# motors_motherBoard_simple_panel.net
KiCad netlist of a schematic drawn in EAGLE
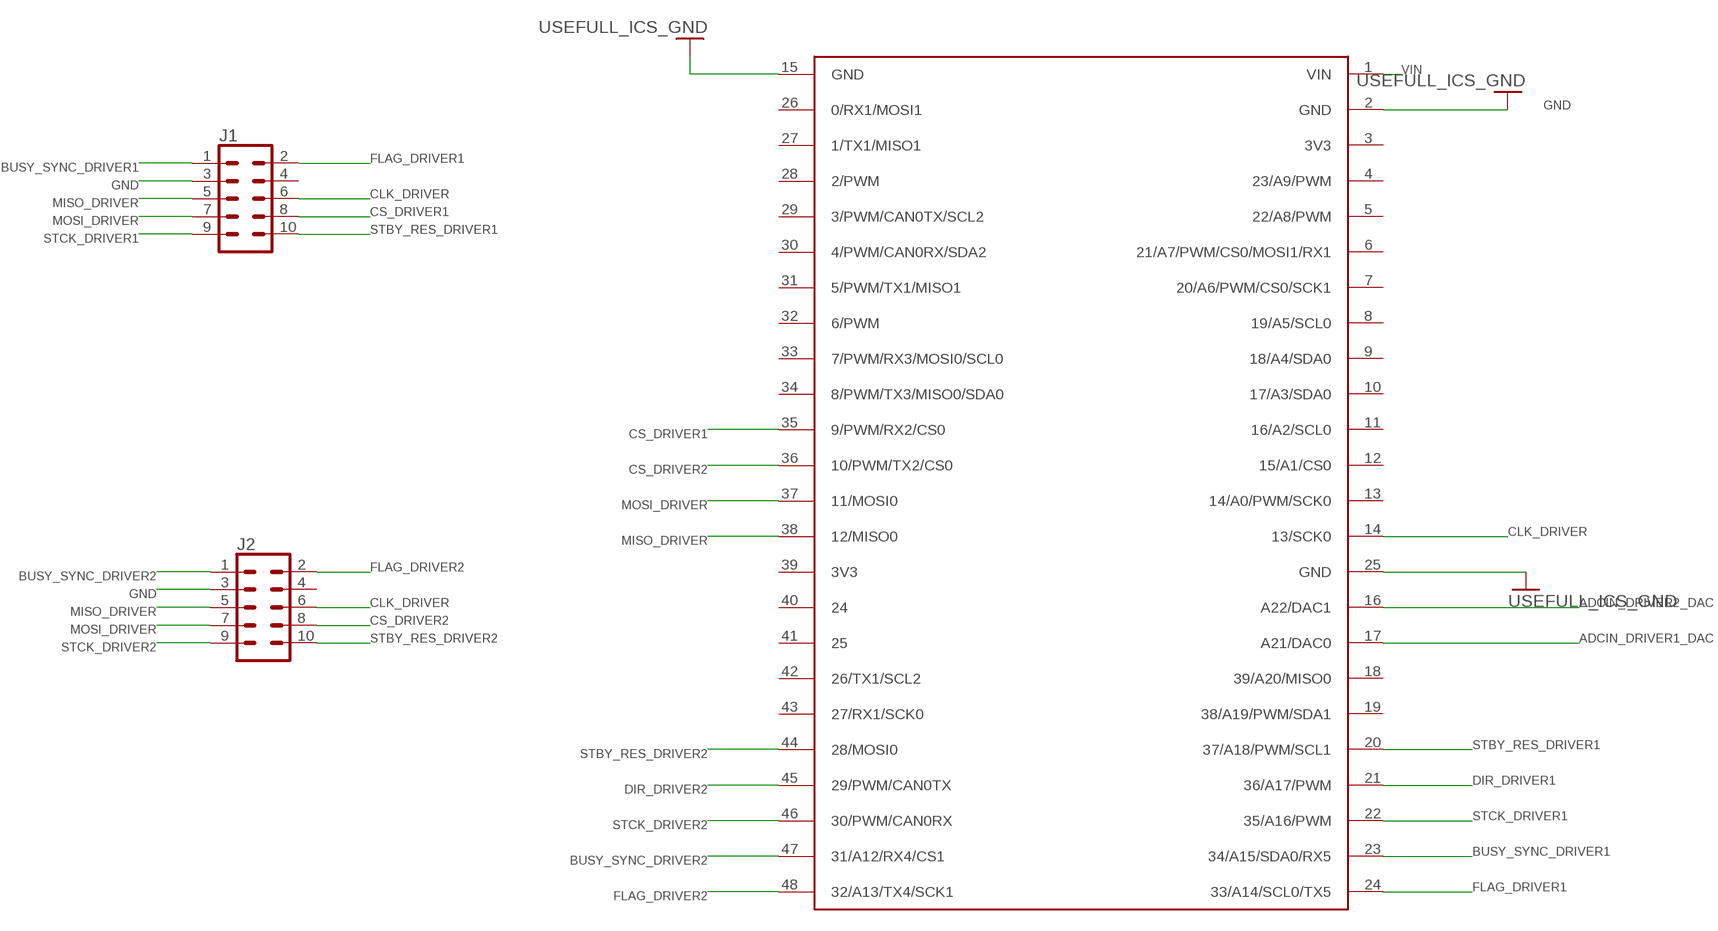
[diagram p0: schematic, sheet 1]
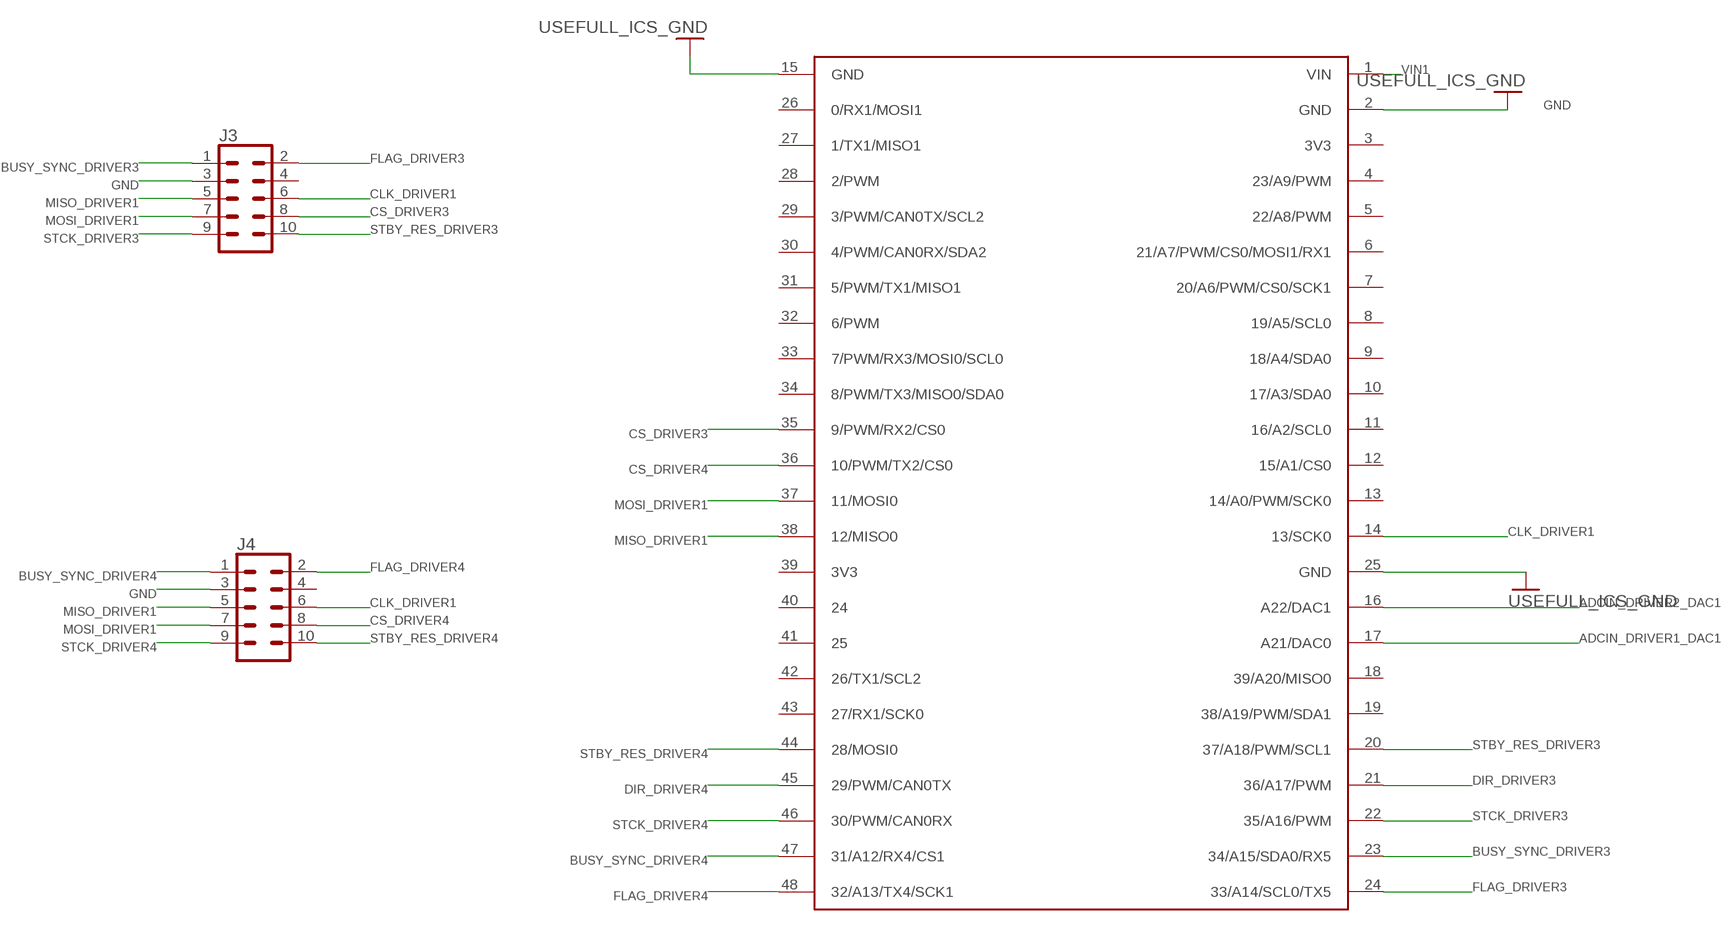
[diagram p1: schematic, sheet 2]

(export (version "E")
  (design (tool "Eeschema 10.0.6"))
  (components
    (comp (ref "J3")
      (value "SPARKFUN-CONNECTORS_CONN_05X2SHD_LOCK")
      (footprint "eagle-import:SPARKFUN-CONNECTORS_2X5-SHROUDED_LOCK")
      (libsource (lib "eagle-import") (part "SPARKFUN-CONNECTORS_CONN_05X2SHD_LOCK"))
    )
    (comp (ref "J4")
      (value "SPARKFUN-CONNECTORS_CONN_05X2SHD_LOCK")
      (footprint "eagle-import:SPARKFUN-CONNECTORS_2X5-SHROUDED_LOCK")
      (libsource (lib "eagle-import") (part "SPARKFUN-CONNECTORS_CONN_05X2SHD_LOCK"))
    )
    (comp (ref "U$1")
      (value "USEFULL_ICS_TEENSY_BASE_ADAPTER")
      (footprint "eagle-import:USEFULL_ICS_TEENSY_BASE_ADAPTER")
      (libsource (lib "eagle-import") (part "USEFULL_ICS_TEENSY_BASE_ADAPTER"))
    )
    (comp (ref "J1")
      (value "SPARKFUN-CONNECTORS_CONN_05X2SHD_LOCK")
      (footprint "eagle-import:SPARKFUN-CONNECTORS_2X5-SHROUDED_LOCK")
      (libsource (lib "eagle-import") (part "SPARKFUN-CONNECTORS_CONN_05X2SHD_LOCK"))
    )
    (comp (ref "J2")
      (value "SPARKFUN-CONNECTORS_CONN_05X2SHD_LOCK")
      (footprint "eagle-import:SPARKFUN-CONNECTORS_2X5-SHROUDED_LOCK")
      (libsource (lib "eagle-import") (part "SPARKFUN-CONNECTORS_CONN_05X2SHD_LOCK"))
    )
    (comp (ref "U$3")
      (value "USEFULL_ICS_TEENSY_BASE_ADAPTER")
      (footprint "eagle-import:USEFULL_ICS_TEENSY_BASE_ADAPTER")
      (libsource (lib "eagle-import") (part "USEFULL_ICS_TEENSY_BASE_ADAPTER"))
    )
  )
  (nets
    (net (code "1") (name "ADCIN_DRIVER1_DAC") (class "Default")
      (node (ref "U$3") (pin "17") (pinfunction "A21/DAC0_17") (pintype "bidirectional"))
    )
    (net (code "2") (name "ADCIN_DRIVER1_DAC1") (class "Default")
      (node (ref "U$1") (pin "17") (pinfunction "A21/DAC0_17") (pintype "bidirectional"))
    )
    (net (code "3") (name "ADCIN_DRIVER2_DAC") (class "Default")
      (node (ref "U$3") (pin "16") (pinfunction "A22/DAC1_16") (pintype "bidirectional"))
    )
    (net (code "4") (name "ADCIN_DRIVER2_DAC1") (class "Default")
      (node (ref "U$1") (pin "16") (pinfunction "A22/DAC1_16") (pintype "bidirectional"))
    )
    (net (code "5") (name "BUSY_SYNC_DRIVER1") (class "Default")
      (node (ref "J1") (pin "1") (pinfunction "1_1") (pintype "passive"))
      (node (ref "U$3") (pin "23") (pinfunction "34/A15/SDA0/RX5_23") (pintype "bidirectional"))
    )
    (net (code "6") (name "BUSY_SYNC_DRIVER2") (class "Default")
      (node (ref "J2") (pin "1") (pinfunction "1_1") (pintype "passive"))
      (node (ref "U$3") (pin "47") (pinfunction "31/A12/RX4/CS1_47") (pintype "bidirectional"))
    )
    (net (code "7") (name "BUSY_SYNC_DRIVER3") (class "Default")
      (node (ref "J3") (pin "1") (pinfunction "1_1") (pintype "passive"))
      (node (ref "U$1") (pin "23") (pinfunction "34/A15/SDA0/RX5_23") (pintype "bidirectional"))
    )
    (net (code "8") (name "BUSY_SYNC_DRIVER4") (class "Default")
      (node (ref "J4") (pin "1") (pinfunction "1_1") (pintype "passive"))
      (node (ref "U$1") (pin "47") (pinfunction "31/A12/RX4/CS1_47") (pintype "bidirectional"))
    )
    (net (code "9") (name "CLK_DRIVER") (class "Default")
      (node (ref "J1") (pin "6") (pinfunction "6_6") (pintype "passive"))
      (node (ref "J2") (pin "6") (pinfunction "6_6") (pintype "passive"))
      (node (ref "U$3") (pin "14") (pinfunction "13/SCK0_14") (pintype "bidirectional"))
    )
    (net (code "10") (name "CLK_DRIVER1") (class "Default")
      (node (ref "J3") (pin "6") (pinfunction "6_6") (pintype "passive"))
      (node (ref "J4") (pin "6") (pinfunction "6_6") (pintype "passive"))
      (node (ref "U$1") (pin "14") (pinfunction "13/SCK0_14") (pintype "bidirectional"))
    )
    (net (code "11") (name "CS_DRIVER1") (class "Default")
      (node (ref "J1") (pin "8") (pinfunction "8_8") (pintype "passive"))
      (node (ref "U$3") (pin "35") (pinfunction "9/PWM/RX2/CS0_35") (pintype "bidirectional"))
    )
    (net (code "12") (name "CS_DRIVER2") (class "Default")
      (node (ref "J2") (pin "8") (pinfunction "8_8") (pintype "passive"))
      (node (ref "U$3") (pin "36") (pinfunction "10/PWM/TX2/CS0_36") (pintype "bidirectional"))
    )
    (net (code "13") (name "CS_DRIVER3") (class "Default")
      (node (ref "J3") (pin "8") (pinfunction "8_8") (pintype "passive"))
      (node (ref "U$1") (pin "35") (pinfunction "9/PWM/RX2/CS0_35") (pintype "bidirectional"))
    )
    (net (code "14") (name "CS_DRIVER4") (class "Default")
      (node (ref "J4") (pin "8") (pinfunction "8_8") (pintype "passive"))
      (node (ref "U$1") (pin "36") (pinfunction "10/PWM/TX2/CS0_36") (pintype "bidirectional"))
    )
    (net (code "15") (name "DIR_DRIVER1") (class "Default")
      (node (ref "U$3") (pin "21") (pinfunction "36/A17/PWM_21") (pintype "bidirectional"))
    )
    (net (code "16") (name "DIR_DRIVER2") (class "Default")
      (node (ref "U$3") (pin "45") (pinfunction "29/PWM/CAN0TX_45") (pintype "bidirectional"))
    )
    (net (code "17") (name "DIR_DRIVER3") (class "Default")
      (node (ref "U$1") (pin "21") (pinfunction "36/A17/PWM_21") (pintype "bidirectional"))
    )
    (net (code "18") (name "DIR_DRIVER4") (class "Default")
      (node (ref "U$1") (pin "45") (pinfunction "29/PWM/CAN0TX_45") (pintype "bidirectional"))
    )
    (net (code "19") (name "FLAG_DRIVER1") (class "Default")
      (node (ref "J1") (pin "2") (pinfunction "2_2") (pintype "passive"))
      (node (ref "U$3") (pin "24") (pinfunction "33/A14/SCL0/TX5_24") (pintype "bidirectional"))
    )
    (net (code "20") (name "FLAG_DRIVER2") (class "Default")
      (node (ref "J2") (pin "2") (pinfunction "2_2") (pintype "passive"))
      (node (ref "U$3") (pin "48") (pinfunction "32/A13/TX4/SCK1_48") (pintype "bidirectional"))
    )
    (net (code "21") (name "FLAG_DRIVER3") (class "Default")
      (node (ref "J3") (pin "2") (pinfunction "2_2") (pintype "passive"))
      (node (ref "U$1") (pin "24") (pinfunction "33/A14/SCL0/TX5_24") (pintype "bidirectional"))
    )
    (net (code "22") (name "FLAG_DRIVER4") (class "Default")
      (node (ref "J4") (pin "2") (pinfunction "2_2") (pintype "passive"))
      (node (ref "U$1") (pin "48") (pinfunction "32/A13/TX4/SCK1_48") (pintype "bidirectional"))
    )
    (net (code "23") (name "GND") (class "Default")
      (node (ref "J1") (pin "3") (pinfunction "3_3") (pintype "passive"))
      (node (ref "J2") (pin "3") (pinfunction "3_3") (pintype "passive"))
      (node (ref "J3") (pin "3") (pinfunction "3_3") (pintype "passive"))
      (node (ref "J4") (pin "3") (pinfunction "3_3") (pintype "passive"))
      (node (ref "U$1") (pin "15") (pinfunction "GND_15") (pintype "bidirectional"))
      (node (ref "U$1") (pin "2") (pinfunction "GND_2") (pintype "bidirectional"))
      (node (ref "U$1") (pin "25") (pinfunction "GND_25") (pintype "bidirectional"))
      (node (ref "U$3") (pin "15") (pinfunction "GND_15") (pintype "bidirectional"))
      (node (ref "U$3") (pin "2") (pinfunction "GND_2") (pintype "bidirectional"))
      (node (ref "U$3") (pin "25") (pinfunction "GND_25") (pintype "bidirectional"))
    )
    (net (code "24") (name "MISO_DRIVER") (class "Default")
      (node (ref "J1") (pin "5") (pinfunction "5_5") (pintype "passive"))
      (node (ref "J2") (pin "5") (pinfunction "5_5") (pintype "passive"))
      (node (ref "U$3") (pin "38") (pinfunction "12/MISO0_38") (pintype "bidirectional"))
    )
    (net (code "25") (name "MISO_DRIVER1") (class "Default")
      (node (ref "J3") (pin "5") (pinfunction "5_5") (pintype "passive"))
      (node (ref "J4") (pin "5") (pinfunction "5_5") (pintype "passive"))
      (node (ref "U$1") (pin "38") (pinfunction "12/MISO0_38") (pintype "bidirectional"))
    )
    (net (code "26") (name "MOSI_DRIVER") (class "Default")
      (node (ref "J1") (pin "7") (pinfunction "7_7") (pintype "passive"))
      (node (ref "J2") (pin "7") (pinfunction "7_7") (pintype "passive"))
      (node (ref "U$3") (pin "37") (pinfunction "11/MOSI0_37") (pintype "bidirectional"))
    )
    (net (code "27") (name "MOSI_DRIVER1") (class "Default")
      (node (ref "J3") (pin "7") (pinfunction "7_7") (pintype "passive"))
      (node (ref "J4") (pin "7") (pinfunction "7_7") (pintype "passive"))
      (node (ref "U$1") (pin "37") (pinfunction "11/MOSI0_37") (pintype "bidirectional"))
    )
    (net (code "28") (name "STBY_RES_DRIVER1") (class "Default")
      (node (ref "J1") (pin "10") (pinfunction "10_10") (pintype "passive"))
      (node (ref "U$3") (pin "20") (pinfunction "37/A18/PWM/SCL1_20") (pintype "bidirectional"))
    )
    (net (code "29") (name "STBY_RES_DRIVER2") (class "Default")
      (node (ref "J2") (pin "10") (pinfunction "10_10") (pintype "passive"))
      (node (ref "U$3") (pin "44") (pinfunction "28/MOSI0_44") (pintype "bidirectional"))
    )
    (net (code "30") (name "STBY_RES_DRIVER3") (class "Default")
      (node (ref "J3") (pin "10") (pinfunction "10_10") (pintype "passive"))
      (node (ref "U$1") (pin "20") (pinfunction "37/A18/PWM/SCL1_20") (pintype "bidirectional"))
    )
    (net (code "31") (name "STBY_RES_DRIVER4") (class "Default")
      (node (ref "J4") (pin "10") (pinfunction "10_10") (pintype "passive"))
      (node (ref "U$1") (pin "44") (pinfunction "28/MOSI0_44") (pintype "bidirectional"))
    )
    (net (code "32") (name "STCK_DRIVER1") (class "Default")
      (node (ref "J1") (pin "9") (pinfunction "9_9") (pintype "passive"))
      (node (ref "U$3") (pin "22") (pinfunction "35/A16/PWM_22") (pintype "bidirectional"))
    )
    (net (code "33") (name "STCK_DRIVER2") (class "Default")
      (node (ref "J2") (pin "9") (pinfunction "9_9") (pintype "passive"))
      (node (ref "U$3") (pin "46") (pinfunction "30/PWM/CAN0RX_46") (pintype "bidirectional"))
    )
    (net (code "34") (name "STCK_DRIVER3") (class "Default")
      (node (ref "J3") (pin "9") (pinfunction "9_9") (pintype "passive"))
      (node (ref "U$1") (pin "22") (pinfunction "35/A16/PWM_22") (pintype "bidirectional"))
    )
    (net (code "35") (name "STCK_DRIVER4") (class "Default")
      (node (ref "J4") (pin "9") (pinfunction "9_9") (pintype "passive"))
      (node (ref "U$1") (pin "46") (pinfunction "30/PWM/CAN0RX_46") (pintype "bidirectional"))
    )
    (net (code "36") (name "VIN") (class "Default")
      (node (ref "U$3") (pin "1") (pinfunction "VIN_1") (pintype "bidirectional"))
    )
    (net (code "37") (name "VIN1") (class "Default")
      (node (ref "U$1") (pin "1") (pinfunction "VIN_1") (pintype "bidirectional"))
    )
    (net (code "38") (name "unconnected-(J1-Pad4)") (class "Default")
      (node (ref "J1") (pin "4") (pinfunction "4_4") (pintype "passive"))
    )
    (net (code "39") (name "unconnected-(J2-Pad4)") (class "Default")
      (node (ref "J2") (pin "4") (pinfunction "4_4") (pintype "passive"))
    )
    (net (code "40") (name "unconnected-(J3-Pad4)") (class "Default")
      (node (ref "J3") (pin "4") (pinfunction "4_4") (pintype "passive"))
    )
    (net (code "41") (name "unconnected-(J4-Pad4)") (class "Default")
      (node (ref "J4") (pin "4") (pinfunction "4_4") (pintype "passive"))
    )
    (net (code "42") (name "unconnected-(U$1-0{slash}RX1{slash}MOSI1-Pad26)") (class "Default")
      (node (ref "U$1") (pin "26") (pinfunction "0/RX1/MOSI1_26") (pintype "bidirectional"))
    )
    (net (code "43") (name "unconnected-(U$1-1{slash}TX1{slash}MISO1-Pad27)") (class "Default")
      (node (ref "U$1") (pin "27") (pinfunction "1/TX1/MISO1_27") (pintype "bidirectional"))
    )
    (net (code "44") (name "unconnected-(U$1-2{slash}PWM-Pad28)") (class "Default")
      (node (ref "U$1") (pin "28") (pinfunction "2/PWM_28") (pintype "bidirectional"))
    )
    (net (code "45") (name "unconnected-(U$1-3V3-Pad3)") (class "Default")
      (node (ref "U$1") (pin "3") (pinfunction "3V3_3") (pintype "bidirectional"))
    )
    (net (code "46") (name "unconnected-(U$1-3V3-Pad39)") (class "Default")
      (node (ref "U$1") (pin "39") (pinfunction "3V3_39") (pintype "bidirectional"))
    )
    (net (code "47") (name "unconnected-(U$1-3{slash}PWM{slash}CAN0TX{slash}SCL2-Pad29)") (class "Default")
      (node (ref "U$1") (pin "29") (pinfunction "3/PWM/CAN0TX/SCL2_29") (pintype "bidirectional"))
    )
    (net (code "48") (name "unconnected-(U$1-4{slash}PWM{slash}CAN0RX{slash}SDA2-Pad30)") (class "Default")
      (node (ref "U$1") (pin "30") (pinfunction "4/PWM/CAN0RX/SDA2_30") (pintype "bidirectional"))
    )
    (net (code "49") (name "unconnected-(U$1-5{slash}PWM{slash}TX1{slash}MISO1-Pad31)") (class "Default")
      (node (ref "U$1") (pin "31") (pinfunction "5/PWM/TX1/MISO1_31") (pintype "bidirectional"))
    )
    (net (code "50") (name "unconnected-(U$1-6{slash}PWM-Pad32)") (class "Default")
      (node (ref "U$1") (pin "32") (pinfunction "6/PWM_32") (pintype "bidirectional"))
    )
    (net (code "51") (name "unconnected-(U$1-7{slash}PWM{slash}RX3{slash}MOSI0{slash}SCL0-Pad33)") (class "Default")
      (node (ref "U$1") (pin "33") (pinfunction "7/PWM/RX3/MOSI0/SCL0_33") (pintype "bidirectional"))
    )
    (net (code "52") (name "unconnected-(U$1-8{slash}PWM{slash}TX3{slash}MISO0{slash}SDA0-Pad34)") (class "Default")
      (node (ref "U$1") (pin "34") (pinfunction "8/PWM/TX3/MISO0/SDA0_34") (pintype "bidirectional"))
    )
    (net (code "53") (name "unconnected-(U$1-14{slash}A0{slash}PWM{slash}SCK0-Pad13)") (class "Default")
      (node (ref "U$1") (pin "13") (pinfunction "14/A0/PWM/SCK0_13") (pintype "bidirectional"))
    )
    (net (code "54") (name "unconnected-(U$1-15{slash}A1{slash}CS0-Pad12)") (class "Default")
      (node (ref "U$1") (pin "12") (pinfunction "15/A1/CS0_12") (pintype "bidirectional"))
    )
    (net (code "55") (name "unconnected-(U$1-16{slash}A2{slash}SCL0-Pad11)") (class "Default")
      (node (ref "U$1") (pin "11") (pinfunction "16/A2/SCL0_11") (pintype "bidirectional"))
    )
    (net (code "56") (name "unconnected-(U$1-17{slash}A3{slash}SDA0-Pad10)") (class "Default")
      (node (ref "U$1") (pin "10") (pinfunction "17/A3/SDA0_10") (pintype "bidirectional"))
    )
    (net (code "57") (name "unconnected-(U$1-18{slash}A4{slash}SDA0-Pad9)") (class "Default")
      (node (ref "U$1") (pin "9") (pinfunction "18/A4/SDA0_9") (pintype "bidirectional"))
    )
    (net (code "58") (name "unconnected-(U$1-19{slash}A5{slash}SCL0-Pad8)") (class "Default")
      (node (ref "U$1") (pin "8") (pinfunction "19/A5/SCL0_8") (pintype "bidirectional"))
    )
    (net (code "59") (name "unconnected-(U$1-20{slash}A6{slash}PWM{slash}CS0{slash}SCK1-Pad7)") (class "Default")
      (node (ref "U$1") (pin "7") (pinfunction "20/A6/PWM/CS0/SCK1_7") (pintype "bidirectional"))
    )
    (net (code "60") (name "unconnected-(U$1-21{slash}A7{slash}PWM{slash}CS0{slash}MOSI1{slash}RX1-Pad6)") (class "Default")
      (node (ref "U$1") (pin "6") (pinfunction "21/A7/PWM/CS0/MOSI1/RX1_6") (pintype "bidirectional"))
    )
    (net (code "61") (name "unconnected-(U$1-22{slash}A8{slash}PWM-Pad5)") (class "Default")
      (node (ref "U$1") (pin "5") (pinfunction "22/A8/PWM_5") (pintype "bidirectional"))
    )
    (net (code "62") (name "unconnected-(U$1-23{slash}A9{slash}PWM-Pad4)") (class "Default")
      (node (ref "U$1") (pin "4") (pinfunction "23/A9/PWM_4") (pintype "bidirectional"))
    )
    (net (code "63") (name "unconnected-(U$1-24-Pad40)") (class "Default")
      (node (ref "U$1") (pin "40") (pinfunction "24_40") (pintype "bidirectional"))
    )
    (net (code "64") (name "unconnected-(U$1-25-Pad41)") (class "Default")
      (node (ref "U$1") (pin "41") (pinfunction "25_41") (pintype "bidirectional"))
    )
    (net (code "65") (name "unconnected-(U$1-26{slash}TX1{slash}SCL2-Pad42)") (class "Default")
      (node (ref "U$1") (pin "42") (pinfunction "26/TX1/SCL2_42") (pintype "bidirectional"))
    )
    (net (code "66") (name "unconnected-(U$1-27{slash}RX1{slash}SCK0-Pad43)") (class "Default")
      (node (ref "U$1") (pin "43") (pinfunction "27/RX1/SCK0_43") (pintype "bidirectional"))
    )
    (net (code "67") (name "unconnected-(U$1-38{slash}A19{slash}PWM{slash}SDA1-Pad19)") (class "Default")
      (node (ref "U$1") (pin "19") (pinfunction "38/A19/PWM/SDA1_19") (pintype "bidirectional"))
    )
    (net (code "68") (name "unconnected-(U$1-39{slash}A20{slash}MISO0-Pad18)") (class "Default")
      (node (ref "U$1") (pin "18") (pinfunction "39/A20/MISO0_18") (pintype "bidirectional"))
    )
    (net (code "69") (name "unconnected-(U$3-0{slash}RX1{slash}MOSI1-Pad26)") (class "Default")
      (node (ref "U$3") (pin "26") (pinfunction "0/RX1/MOSI1_26") (pintype "bidirectional"))
    )
    (net (code "70") (name "unconnected-(U$3-1{slash}TX1{slash}MISO1-Pad27)") (class "Default")
      (node (ref "U$3") (pin "27") (pinfunction "1/TX1/MISO1_27") (pintype "bidirectional"))
    )
    (net (code "71") (name "unconnected-(U$3-2{slash}PWM-Pad28)") (class "Default")
      (node (ref "U$3") (pin "28") (pinfunction "2/PWM_28") (pintype "bidirectional"))
    )
    (net (code "72") (name "unconnected-(U$3-3V3-Pad3)") (class "Default")
      (node (ref "U$3") (pin "3") (pinfunction "3V3_3") (pintype "bidirectional"))
    )
    (net (code "73") (name "unconnected-(U$3-3V3-Pad39)") (class "Default")
      (node (ref "U$3") (pin "39") (pinfunction "3V3_39") (pintype "bidirectional"))
    )
    (net (code "74") (name "unconnected-(U$3-3{slash}PWM{slash}CAN0TX{slash}SCL2-Pad29)") (class "Default")
      (node (ref "U$3") (pin "29") (pinfunction "3/PWM/CAN0TX/SCL2_29") (pintype "bidirectional"))
    )
    (net (code "75") (name "unconnected-(U$3-4{slash}PWM{slash}CAN0RX{slash}SDA2-Pad30)") (class "Default")
      (node (ref "U$3") (pin "30") (pinfunction "4/PWM/CAN0RX/SDA2_30") (pintype "bidirectional"))
    )
    (net (code "76") (name "unconnected-(U$3-5{slash}PWM{slash}TX1{slash}MISO1-Pad31)") (class "Default")
      (node (ref "U$3") (pin "31") (pinfunction "5/PWM/TX1/MISO1_31") (pintype "bidirectional"))
    )
    (net (code "77") (name "unconnected-(U$3-6{slash}PWM-Pad32)") (class "Default")
      (node (ref "U$3") (pin "32") (pinfunction "6/PWM_32") (pintype "bidirectional"))
    )
    (net (code "78") (name "unconnected-(U$3-7{slash}PWM{slash}RX3{slash}MOSI0{slash}SCL0-Pad33)") (class "Default")
      (node (ref "U$3") (pin "33") (pinfunction "7/PWM/RX3/MOSI0/SCL0_33") (pintype "bidirectional"))
    )
    (net (code "79") (name "unconnected-(U$3-8{slash}PWM{slash}TX3{slash}MISO0{slash}SDA0-Pad34)") (class "Default")
      (node (ref "U$3") (pin "34") (pinfunction "8/PWM/TX3/MISO0/SDA0_34") (pintype "bidirectional"))
    )
    (net (code "80") (name "unconnected-(U$3-14{slash}A0{slash}PWM{slash}SCK0-Pad13)") (class "Default")
      (node (ref "U$3") (pin "13") (pinfunction "14/A0/PWM/SCK0_13") (pintype "bidirectional"))
    )
    (net (code "81") (name "unconnected-(U$3-15{slash}A1{slash}CS0-Pad12)") (class "Default")
      (node (ref "U$3") (pin "12") (pinfunction "15/A1/CS0_12") (pintype "bidirectional"))
    )
    (net (code "82") (name "unconnected-(U$3-16{slash}A2{slash}SCL0-Pad11)") (class "Default")
      (node (ref "U$3") (pin "11") (pinfunction "16/A2/SCL0_11") (pintype "bidirectional"))
    )
    (net (code "83") (name "unconnected-(U$3-17{slash}A3{slash}SDA0-Pad10)") (class "Default")
      (node (ref "U$3") (pin "10") (pinfunction "17/A3/SDA0_10") (pintype "bidirectional"))
    )
    (net (code "84") (name "unconnected-(U$3-18{slash}A4{slash}SDA0-Pad9)") (class "Default")
      (node (ref "U$3") (pin "9") (pinfunction "18/A4/SDA0_9") (pintype "bidirectional"))
    )
    (net (code "85") (name "unconnected-(U$3-19{slash}A5{slash}SCL0-Pad8)") (class "Default")
      (node (ref "U$3") (pin "8") (pinfunction "19/A5/SCL0_8") (pintype "bidirectional"))
    )
    (net (code "86") (name "unconnected-(U$3-20{slash}A6{slash}PWM{slash}CS0{slash}SCK1-Pad7)") (class "Default")
      (node (ref "U$3") (pin "7") (pinfunction "20/A6/PWM/CS0/SCK1_7") (pintype "bidirectional"))
    )
    (net (code "87") (name "unconnected-(U$3-21{slash}A7{slash}PWM{slash}CS0{slash}MOSI1{slash}RX1-Pad6)") (class "Default")
      (node (ref "U$3") (pin "6") (pinfunction "21/A7/PWM/CS0/MOSI1/RX1_6") (pintype "bidirectional"))
    )
    (net (code "88") (name "unconnected-(U$3-22{slash}A8{slash}PWM-Pad5)") (class "Default")
      (node (ref "U$3") (pin "5") (pinfunction "22/A8/PWM_5") (pintype "bidirectional"))
    )
    (net (code "89") (name "unconnected-(U$3-23{slash}A9{slash}PWM-Pad4)") (class "Default")
      (node (ref "U$3") (pin "4") (pinfunction "23/A9/PWM_4") (pintype "bidirectional"))
    )
    (net (code "90") (name "unconnected-(U$3-24-Pad40)") (class "Default")
      (node (ref "U$3") (pin "40") (pinfunction "24_40") (pintype "bidirectional"))
    )
    (net (code "91") (name "unconnected-(U$3-25-Pad41)") (class "Default")
      (node (ref "U$3") (pin "41") (pinfunction "25_41") (pintype "bidirectional"))
    )
    (net (code "92") (name "unconnected-(U$3-26{slash}TX1{slash}SCL2-Pad42)") (class "Default")
      (node (ref "U$3") (pin "42") (pinfunction "26/TX1/SCL2_42") (pintype "bidirectional"))
    )
    (net (code "93") (name "unconnected-(U$3-27{slash}RX1{slash}SCK0-Pad43)") (class "Default")
      (node (ref "U$3") (pin "43") (pinfunction "27/RX1/SCK0_43") (pintype "bidirectional"))
    )
    (net (code "94") (name "unconnected-(U$3-38{slash}A19{slash}PWM{slash}SDA1-Pad19)") (class "Default")
      (node (ref "U$3") (pin "19") (pinfunction "38/A19/PWM/SDA1_19") (pintype "bidirectional"))
    )
    (net (code "95") (name "unconnected-(U$3-39{slash}A20{slash}MISO0-Pad18)") (class "Default")
      (node (ref "U$3") (pin "18") (pinfunction "39/A20/MISO0_18") (pintype "bidirectional"))
    )
  )
)
